# kitt_0805.net
KiCad netlist of a schematic drawn in EAGLE
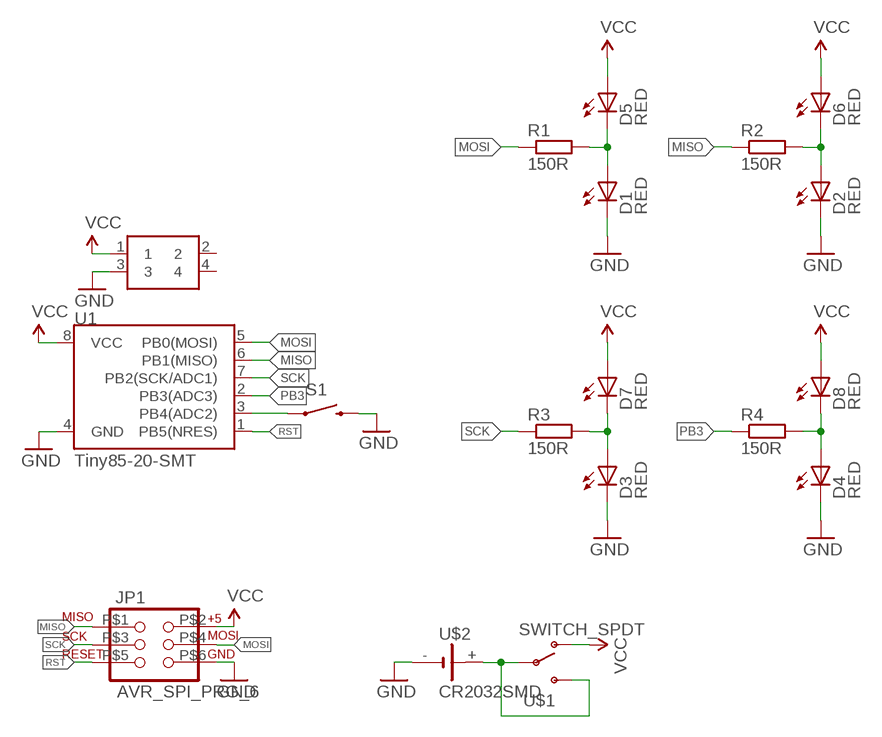
[diagram p0: schematic, sheet 1]

(export (version "E")
  (design (tool "Eeschema 10.0.6"))
  (components
    (comp (ref "D1")
      (value "RED")
      (footprint "eagle-import:CHIP-LED0805")
      (libsource (lib "eagle-import") (part "LEDCHIP-LED0805"))
    )
    (comp (ref "D2")
      (value "RED")
      (footprint "eagle-import:CHIP-LED0805")
      (libsource (lib "eagle-import") (part "LEDCHIP-LED0805"))
    )
    (comp (ref "D3")
      (value "RED")
      (footprint "eagle-import:CHIP-LED0805")
      (libsource (lib "eagle-import") (part "LEDCHIP-LED0805"))
    )
    (comp (ref "D4")
      (value "RED")
      (footprint "eagle-import:CHIP-LED0805")
      (libsource (lib "eagle-import") (part "LEDCHIP-LED0805"))
    )
    (comp (ref "D5")
      (value "RED")
      (footprint "eagle-import:CHIP-LED0805")
      (libsource (lib "eagle-import") (part "LEDCHIP-LED0805"))
    )
    (comp (ref "D6")
      (value "RED")
      (footprint "eagle-import:CHIP-LED0805")
      (libsource (lib "eagle-import") (part "LEDCHIP-LED0805"))
    )
    (comp (ref "D7")
      (value "RED")
      (footprint "eagle-import:CHIP-LED0805")
      (libsource (lib "eagle-import") (part "LEDCHIP-LED0805"))
    )
    (comp (ref "D8")
      (value "RED")
      (footprint "eagle-import:CHIP-LED0805")
      (libsource (lib "eagle-import") (part "LEDCHIP-LED0805"))
    )
    (comp (ref "JP1")
      (value "AVR_SPI_PRG_6")
      (footprint "eagle-import:2X3_SMD_PAD")
      (libsource (lib "eagle-import") (part "AVR_SPI_PRG_6"))
    )
    (comp (ref "R1")
      (value "150R")
      (footprint "eagle-import:M0805")
      (libsource (lib "eagle-import") (part "R-EU_M0805"))
    )
    (comp (ref "R2")
      (value "150R")
      (footprint "eagle-import:M0805")
      (libsource (lib "eagle-import") (part "R-EU_M0805"))
    )
    (comp (ref "R3")
      (value "150R")
      (footprint "eagle-import:M0805")
      (libsource (lib "eagle-import") (part "R-EU_M0805"))
    )
    (comp (ref "R4")
      (value "150R")
      (footprint "eagle-import:M0805")
      (libsource (lib "eagle-import") (part "R-EU_M0805"))
    )
    (comp (ref "S1")
      (value "SWITCH-MOMENTARY-2-SMD-1101NE")
      (footprint "eagle-import:TACTILE-SWITCH-1101NE")
      (libsource (lib "eagle-import") (part "SWITCH-MOMENTARY-2-SMD-1101NE"))
    )
    (comp (ref "U$1")
      (value "SWITCH_SPDT")
      (footprint "eagle-import:KPS-1290")
      (libsource (lib "eagle-import") (part "SWITCH_SPDT"))
    )
    (comp (ref "U$2")
      (value "CR2032SMD")
      (footprint "eagle-import:CR2032SMD")
      (libsource (lib "eagle-import") (part "CR2032SMD"))
    )
    (comp (ref "U$4")
      (value "2X2-SMT")
      (footprint "eagle-import:2X2-SMT")
      (libsource (lib "eagle-import") (part "2X2-SMT"))
    )
    (comp (ref "U1")
      (value "Tiny85-20-SMT")
      (footprint "eagle-import:SO08-EIAJ")
      (libsource (lib "eagle-import") (part "ATTINY45TINY85-20-SMT"))
    )
  )
  (nets
    (net (code "1") (name "GND") (class "Default")
      (node (ref "D1") (pin "C") (pinfunction "C_C") (pintype "passive"))
      (node (ref "D2") (pin "C") (pinfunction "C_C") (pintype "passive"))
      (node (ref "D3") (pin "C") (pinfunction "C_C") (pintype "passive"))
      (node (ref "D4") (pin "C") (pinfunction "C_C") (pintype "passive"))
      (node (ref "JP1") (pin "P$6") (pinfunction "6_P$6") (pintype "passive"))
      (node (ref "S1") (pin "P$2") (pinfunction "2_P$2") (pintype "passive"))
      (node (ref "U$2") (pin "-") (pinfunction "-_-") (pintype "passive"))
      (node (ref "U$4") (pin "3") (pinfunction "3_3") (pintype "bidirectional"))
      (node (ref "U1") (pin "4") (pinfunction "GND_4") (pintype "bidirectional"))
    )
    (net (code "2") (name "MISO") (class "Default")
      (node (ref "JP1") (pin "P$1") (pinfunction "1_P$1") (pintype "passive"))
      (node (ref "R2") (pin "1") (pinfunction "1_1") (pintype "passive"))
      (node (ref "U1") (pin "6") (pinfunction "PB1(MISO)_6") (pintype "bidirectional"))
    )
    (net (code "3") (name "MOSI") (class "Default")
      (node (ref "JP1") (pin "P$4") (pinfunction "4_P$4") (pintype "passive"))
      (node (ref "R1") (pin "1") (pinfunction "1_1") (pintype "passive"))
      (node (ref "U1") (pin "5") (pinfunction "PB0(MOSI)_5") (pintype "bidirectional"))
    )
    (net (code "4") (name "Net-(D1-PadA)") (class "Default")
      (node (ref "D1") (pin "A") (pinfunction "A_A") (pintype "passive"))
      (node (ref "D5") (pin "C") (pinfunction "C_C") (pintype "passive"))
      (node (ref "R1") (pin "2") (pinfunction "2_2") (pintype "passive"))
    )
    (net (code "5") (name "Net-(D2-PadA)") (class "Default")
      (node (ref "D2") (pin "A") (pinfunction "A_A") (pintype "passive"))
      (node (ref "D6") (pin "C") (pinfunction "C_C") (pintype "passive"))
      (node (ref "R2") (pin "2") (pinfunction "2_2") (pintype "passive"))
    )
    (net (code "6") (name "Net-(D3-PadA)") (class "Default")
      (node (ref "D3") (pin "A") (pinfunction "A_A") (pintype "passive"))
      (node (ref "D7") (pin "C") (pinfunction "C_C") (pintype "passive"))
      (node (ref "R3") (pin "2") (pinfunction "2_2") (pintype "passive"))
    )
    (net (code "7") (name "Net-(D4-PadA)") (class "Default")
      (node (ref "D4") (pin "A") (pinfunction "A_A") (pintype "passive"))
      (node (ref "D8") (pin "C") (pinfunction "C_C") (pintype "passive"))
      (node (ref "R4") (pin "2") (pinfunction "2_2") (pintype "passive"))
    )
    (net (code "8") (name "Net-(S1-1)") (class "Default")
      (node (ref "S1") (pin "P$1") (pinfunction "1_P$1") (pintype "passive"))
      (node (ref "U1") (pin "3") (pinfunction "PB4(ADC2)_3") (pintype "bidirectional"))
    )
    (net (code "9") (name "Net-(U$1-PadP)") (class "Default")
      (node (ref "U$1") (pin "P") (pinfunction "P_P") (pintype "passive"))
      (node (ref "U$1") (pin "S") (pinfunction "S_S") (pintype "passive"))
      (node (ref "U$2") (pin "+") (pinfunction "+_+") (pintype "passive"))
    )
    (net (code "10") (name "PB3") (class "Default")
      (node (ref "R4") (pin "1") (pinfunction "1_1") (pintype "passive"))
      (node (ref "U1") (pin "2") (pinfunction "PB3(ADC3)_2") (pintype "bidirectional"))
    )
    (net (code "11") (name "RST") (class "Default")
      (node (ref "JP1") (pin "P$5") (pinfunction "5_P$5") (pintype "passive"))
      (node (ref "U1") (pin "1") (pinfunction "PB5(NRES)_1") (pintype "bidirectional"))
    )
    (net (code "12") (name "SCK") (class "Default")
      (node (ref "JP1") (pin "P$3") (pinfunction "3_P$3") (pintype "passive"))
      (node (ref "R3") (pin "1") (pinfunction "1_1") (pintype "passive"))
      (node (ref "U1") (pin "7") (pinfunction "PB2(SCK/ADC1)_7") (pintype "bidirectional"))
    )
    (net (code "13") (name "VCC") (class "Default")
      (node (ref "D5") (pin "A") (pinfunction "A_A") (pintype "passive"))
      (node (ref "D6") (pin "A") (pinfunction "A_A") (pintype "passive"))
      (node (ref "D7") (pin "A") (pinfunction "A_A") (pintype "passive"))
      (node (ref "D8") (pin "A") (pinfunction "A_A") (pintype "passive"))
      (node (ref "JP1") (pin "P$2") (pinfunction "2_P$2") (pintype "passive"))
      (node (ref "U$1") (pin "O") (pinfunction "O_O") (pintype "passive"))
      (node (ref "U$4") (pin "1") (pinfunction "1_1") (pintype "bidirectional"))
      (node (ref "U1") (pin "8") (pinfunction "VCC_8") (pintype "bidirectional"))
    )
    (net (code "14") (name "unconnected-(U$4-Pad2)") (class "Default")
      (node (ref "U$4") (pin "2") (pinfunction "2_2") (pintype "bidirectional"))
    )
    (net (code "15") (name "unconnected-(U$4-Pad4)") (class "Default")
      (node (ref "U$4") (pin "4") (pinfunction "4_4") (pintype "bidirectional"))
    )
  )
)
